# CtoMicroOTG.net
KiCad netlist of a schematic drawn in Altium Designer
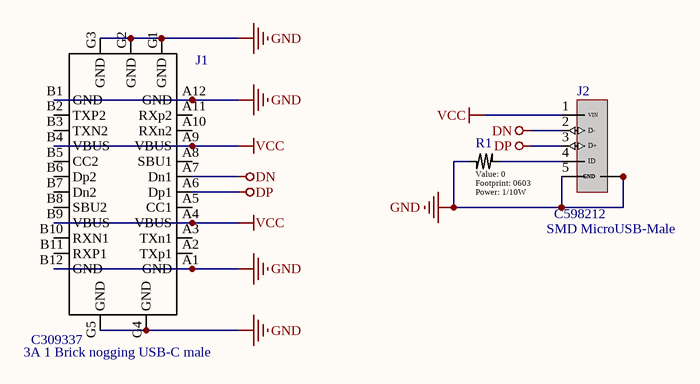
[diagram p0: CtoMicroOTG.SchDoc]

(export (version "E")
  (design (tool "Eeschema 10.0.6"))
  (components
    (comp (ref "J1")
      (value "3A 1 Brick nogging USB-C male")
      (footprint "USB-309GD")
      (description "3A 1 Brick nogging 24P male -20℃~+60℃ Type-C SMD USB Connector")
      (fields (field (name "LCSC PN") "C309337"))
      (libsource (lib "Connectors") (part "USB-309GD"))
    )
    (comp (ref "J2")
      (value "SMD MicroUSB-Male")
      (footprint "ZX80-B-5SA(30)")
      (description "USB 2.0 1 5P Male -30℃~+85℃ Micro-B SMD USB Connector")
      (fields (field (name "LCSC PN") "C598212"))
      (libsource (lib "Connectors") (part "ZX80-B-5SA(30)"))
    )
    (comp (ref "R1")
      (value "0")
      (footprint "0603")
      (fields (field (name "POWER") "1/10W") (field (name "Comment") "Generic Resistor"))
      (libsource (lib "Resistors") (part "Generic Resistor"))
    )
  )
  (nets
    (net (code "1") (name "DN") (class "Default")
      (node (ref "J1") (pin "A7") (pinfunction "Dn1_A7") (pintype "passive"))
      (node (ref "J2") (pin "2") (pinfunction "D-_2") (pintype "bidirectional"))
    )
    (net (code "2") (name "DP") (class "Default")
      (node (ref "J1") (pin "A6") (pinfunction "Dp1_A6") (pintype "passive"))
      (node (ref "J2") (pin "3") (pinfunction "D+_3") (pintype "bidirectional"))
    )
    (net (code "3") (name "GND") (class "Default")
      (node (ref "J1") (pin "A1") (pinfunction "GND_A1") (pintype "passive"))
      (node (ref "J1") (pin "A12") (pinfunction "GND_A12") (pintype "passive"))
      (node (ref "J1") (pin "B1") (pinfunction "GND_B1") (pintype "passive"))
      (node (ref "J1") (pin "B12") (pinfunction "GND_B12") (pintype "passive"))
      (node (ref "J1") (pin "G1") (pinfunction "GND_G1") (pintype "passive"))
      (node (ref "J1") (pin "G2") (pinfunction "GND_G2") (pintype "passive"))
      (node (ref "J1") (pin "G3") (pinfunction "GND_G3") (pintype "passive"))
      (node (ref "J1") (pin "G4") (pinfunction "GND_G4") (pintype "passive"))
      (node (ref "J1") (pin "G5") (pinfunction "GND_G5") (pintype "passive"))
      (node (ref "J2") (pin "5") (pinfunction "GND_5") (pintype "passive"))
      (node (ref "J2") (pin "6") (pinfunction "GND_6") (pintype "passive"))
      (node (ref "J2") (pin "7") (pinfunction "GND_7") (pintype "passive"))
      (node (ref "J2") (pin "8") (pinfunction "GND_8") (pintype "passive"))
      (node (ref "J2") (pin "9") (pinfunction "GND_9") (pintype "passive"))
      (node (ref "R1") (pin "2") (pinfunction "2_2") (pintype "passive"))
    )
    (net (code "4") (name "Net-(J2-ID)") (class "Default")
      (node (ref "J2") (pin "4") (pinfunction "ID_4") (pintype "passive"))
      (node (ref "R1") (pin "1") (pinfunction "1_1") (pintype "passive"))
    )
    (net (code "5") (name "VCC") (class "Default")
      (node (ref "J1") (pin "A4") (pinfunction "VBUS_A4") (pintype "passive"))
      (node (ref "J1") (pin "A9") (pinfunction "VBUS_A9") (pintype "passive"))
      (node (ref "J1") (pin "B4") (pinfunction "VBUS_B4") (pintype "passive"))
      (node (ref "J1") (pin "B9") (pinfunction "VBUS_B9") (pintype "passive"))
      (node (ref "J2") (pin "1") (pinfunction "VIN_1") (pintype "passive"))
    )
    (net (code "6") (name "unconnected-(J1-CC1-PadA5)") (class "Default")
      (node (ref "J1") (pin "A5") (pinfunction "CC1_A5") (pintype "passive"))
    )
    (net (code "7") (name "unconnected-(J1-CC2-PadB5)") (class "Default")
      (node (ref "J1") (pin "B5") (pinfunction "CC2_B5") (pintype "passive"))
    )
    (net (code "8") (name "unconnected-(J1-Dn2-PadB7)") (class "Default")
      (node (ref "J1") (pin "B7") (pinfunction "Dn2_B7") (pintype "passive"))
    )
    (net (code "9") (name "unconnected-(J1-Dp2-PadB6)") (class "Default")
      (node (ref "J1") (pin "B6") (pinfunction "Dp2_B6") (pintype "passive"))
    )
    (net (code "10") (name "unconnected-(J1-RXN1-PadB10)") (class "Default")
      (node (ref "J1") (pin "B10") (pinfunction "RXN1_B10") (pintype "passive"))
    )
    (net (code "11") (name "unconnected-(J1-RXP1-PadB11)") (class "Default")
      (node (ref "J1") (pin "B11") (pinfunction "RXP1_B11") (pintype "passive"))
    )
    (net (code "12") (name "unconnected-(J1-RXn2-PadA10)") (class "Default")
      (node (ref "J1") (pin "A10") (pinfunction "RXn2_A10") (pintype "passive"))
    )
    (net (code "13") (name "unconnected-(J1-RXp2-PadA11)") (class "Default")
      (node (ref "J1") (pin "A11") (pinfunction "RXp2_A11") (pintype "passive"))
    )
    (net (code "14") (name "unconnected-(J1-SBU1-PadA8)") (class "Default")
      (node (ref "J1") (pin "A8") (pinfunction "SBU1_A8") (pintype "passive"))
    )
    (net (code "15") (name "unconnected-(J1-SBU2-PadB8)") (class "Default")
      (node (ref "J1") (pin "B8") (pinfunction "SBU2_B8") (pintype "passive"))
    )
    (net (code "16") (name "unconnected-(J1-TXN2-PadB3)") (class "Default")
      (node (ref "J1") (pin "B3") (pinfunction "TXN2_B3") (pintype "passive"))
    )
    (net (code "17") (name "unconnected-(J1-TXP2-PadB2)") (class "Default")
      (node (ref "J1") (pin "B2") (pinfunction "TXP2_B2") (pintype "passive"))
    )
    (net (code "18") (name "unconnected-(J1-TXn1-PadA3)") (class "Default")
      (node (ref "J1") (pin "A3") (pinfunction "TXn1_A3") (pintype "passive"))
    )
    (net (code "19") (name "unconnected-(J1-TXp1-PadA2)") (class "Default")
      (node (ref "J1") (pin "A2") (pinfunction "TXp1_A2") (pintype "passive"))
    )
  )
)
